# spi_v3.net
KiCad netlist of a schematic drawn in EAGLE
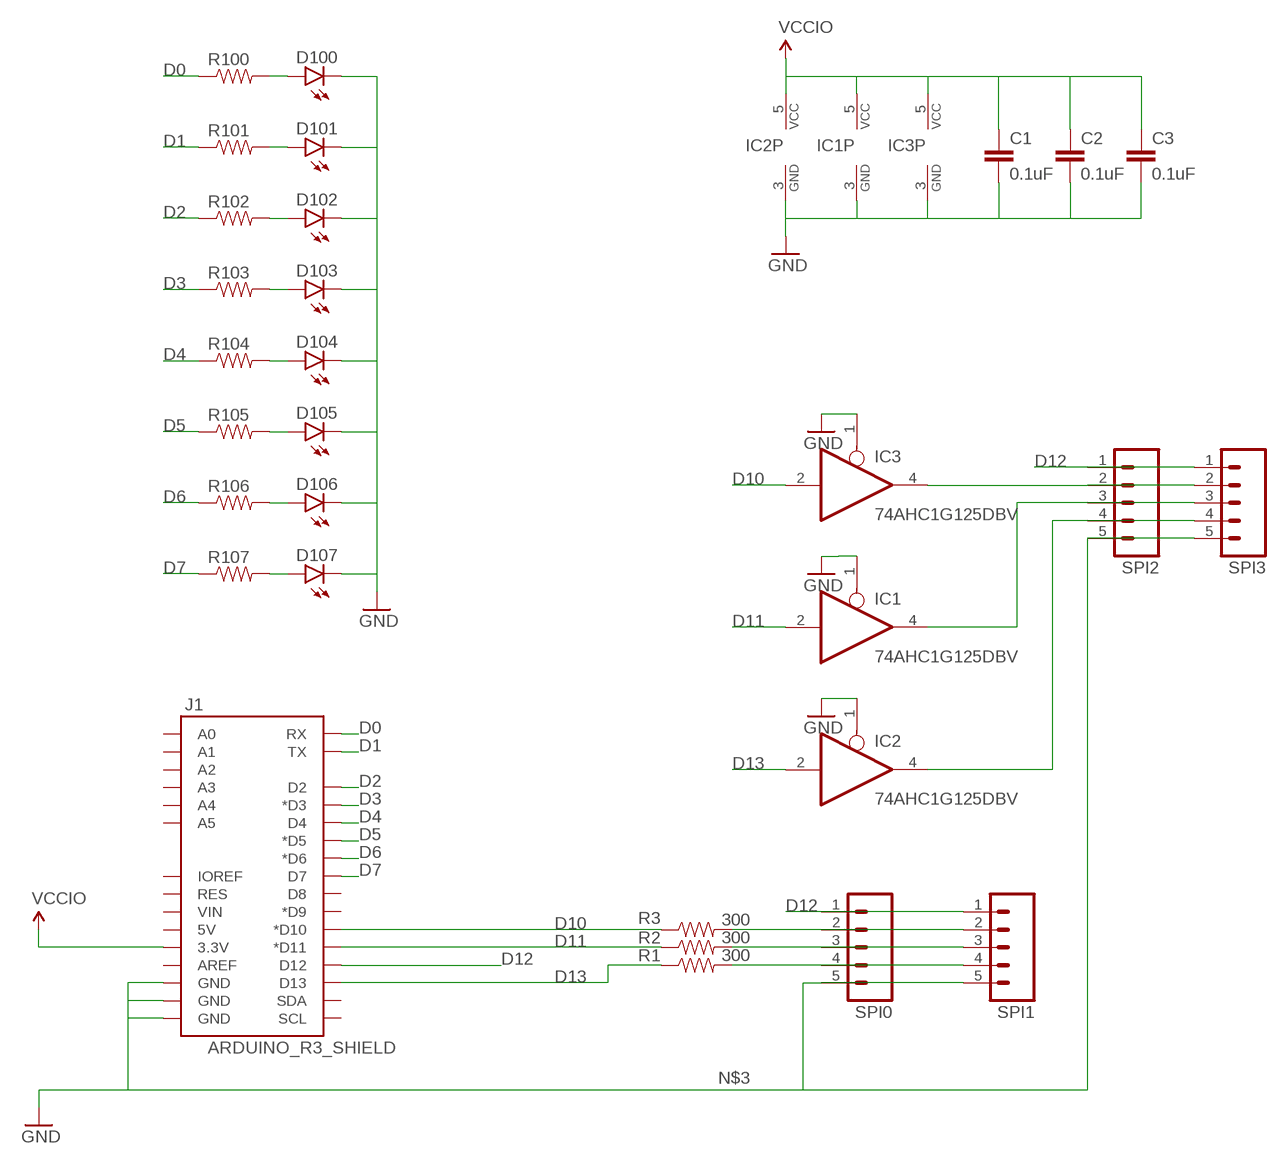
[diagram p0: schematic, sheet 1]

(export (version "E")
  (design (tool "Eeschema 10.0.6"))
  (components
    (comp (ref "C1")
      (value "0.1uF")
      (footprint "eagle-import:0402-CAP")
      (libsource (lib "eagle-import") (part "0.1UF-16V(+-10%)(0402)"))
    )
    (comp (ref "C2")
      (value "0.1uF")
      (footprint "eagle-import:0402-CAP")
      (libsource (lib "eagle-import") (part "0.1UF-16V(+-10%)(0402)"))
    )
    (comp (ref "C3")
      (value "0.1uF")
      (footprint "eagle-import:0402-CAP")
      (libsource (lib "eagle-import") (part "0.1UF-16V(+-10%)(0402)"))
    )
    (comp (ref "D100")
      (value "LED-FKIT-1206")
      (footprint "eagle-import:FKIT-LED-1206")
      (libsource (lib "eagle-import") (part "LED-FKIT-1206"))
    )
    (comp (ref "D101")
      (value "LED-FKIT-1206")
      (footprint "eagle-import:FKIT-LED-1206")
      (libsource (lib "eagle-import") (part "LED-FKIT-1206"))
    )
    (comp (ref "D102")
      (value "LED-FKIT-1206")
      (footprint "eagle-import:FKIT-LED-1206")
      (libsource (lib "eagle-import") (part "LED-FKIT-1206"))
    )
    (comp (ref "D103")
      (value "LED-FKIT-1206")
      (footprint "eagle-import:FKIT-LED-1206")
      (libsource (lib "eagle-import") (part "LED-FKIT-1206"))
    )
    (comp (ref "D104")
      (value "LED-FKIT-1206")
      (footprint "eagle-import:FKIT-LED-1206")
      (libsource (lib "eagle-import") (part "LED-FKIT-1206"))
    )
    (comp (ref "D105")
      (value "LED-FKIT-1206")
      (footprint "eagle-import:FKIT-LED-1206")
      (libsource (lib "eagle-import") (part "LED-FKIT-1206"))
    )
    (comp (ref "D106")
      (value "LED-FKIT-1206")
      (footprint "eagle-import:FKIT-LED-1206")
      (libsource (lib "eagle-import") (part "LED-FKIT-1206"))
    )
    (comp (ref "D107")
      (value "LED-FKIT-1206")
      (footprint "eagle-import:FKIT-LED-1206")
      (libsource (lib "eagle-import") (part "LED-FKIT-1206"))
    )
    (comp (ref "IC1")
      (value "74AHC1G125DBV")
      (footprint "eagle-import:SOT23-5")
      (libsource (lib "eagle-import") (part "741G125DBVAHC"))
    )
    (comp (ref "IC2")
      (value "74AHC1G125DBV")
      (footprint "eagle-import:SOT23-5")
      (libsource (lib "eagle-import") (part "741G125DBVAHC"))
    )
    (comp (ref "IC3")
      (value "74AHC1G125DBV")
      (footprint "eagle-import:SOT23-5")
      (libsource (lib "eagle-import") (part "741G125DBVAHC"))
    )
    (comp (ref "J1")
      (value "ARDUINO_R3_SHIELD")
      (footprint "eagle-import:UNO_R3_SHIELD")
      (libsource (lib "eagle-import") (part "ARDUINO_R3_SHIELD"))
    )
    (comp (ref "R1")
      (value "300")
      (footprint "eagle-import:AXIAL-0.4")
      (libsource (lib "eagle-import") (part "RESISTORPTH-1/4W"))
    )
    (comp (ref "R2")
      (value "300")
      (footprint "eagle-import:AXIAL-0.4")
      (libsource (lib "eagle-import") (part "RESISTORPTH-1/4W"))
    )
    (comp (ref "R3")
      (value "300")
      (footprint "eagle-import:AXIAL-0.4")
      (libsource (lib "eagle-import") (part "RESISTORPTH-1/4W"))
    )
    (comp (ref "R100")
      (value "RESISTOR0805-RES")
      (footprint "eagle-import:0805")
      (libsource (lib "eagle-import") (part "RESISTOR0805-RES"))
    )
    (comp (ref "R101")
      (value "RESISTOR0805-RES")
      (footprint "eagle-import:0805")
      (libsource (lib "eagle-import") (part "RESISTOR0805-RES"))
    )
    (comp (ref "R102")
      (value "RESISTOR0805-RES")
      (footprint "eagle-import:0805")
      (libsource (lib "eagle-import") (part "RESISTOR0805-RES"))
    )
    (comp (ref "R103")
      (value "RESISTOR0805-RES")
      (footprint "eagle-import:0805")
      (libsource (lib "eagle-import") (part "RESISTOR0805-RES"))
    )
    (comp (ref "R104")
      (value "RESISTOR0805-RES")
      (footprint "eagle-import:0805")
      (libsource (lib "eagle-import") (part "RESISTOR0805-RES"))
    )
    (comp (ref "R105")
      (value "RESISTOR0805-RES")
      (footprint "eagle-import:0805")
      (libsource (lib "eagle-import") (part "RESISTOR0805-RES"))
    )
    (comp (ref "R106")
      (value "RESISTOR0805-RES")
      (footprint "eagle-import:0805")
      (libsource (lib "eagle-import") (part "RESISTOR0805-RES"))
    )
    (comp (ref "R107")
      (value "RESISTOR0805-RES")
      (footprint "eagle-import:0805")
      (libsource (lib "eagle-import") (part "RESISTOR0805-RES"))
    )
    (comp (ref "SPI0")
      (value "M05PTH_LONGPADS")
      (footprint "eagle-import:1X05_LONGPADS")
      (libsource (lib "eagle-import") (part "M05PTH_LONGPADS"))
    )
    (comp (ref "SPI1")
      (value "M05PTH_LONGPADS")
      (footprint "eagle-import:1X05_LONGPADS")
      (libsource (lib "eagle-import") (part "M05PTH_LONGPADS"))
    )
    (comp (ref "SPI2")
      (value "M05PTH_LONGPADS")
      (footprint "eagle-import:1X05_LONGPADS")
      (libsource (lib "eagle-import") (part "M05PTH_LONGPADS"))
    )
    (comp (ref "SPI3")
      (value "M05PTH_LONGPADS")
      (footprint "eagle-import:1X05_LONGPADS")
      (libsource (lib "eagle-import") (part "M05PTH_LONGPADS"))
    )
  )
  (nets
    (net (code "1") (name "/D0") (class "Default")
      (node (ref "J1") (pin "RX") (pinfunction "RX_RX") (pintype "bidirectional"))
      (node (ref "R100") (pin "1") (pinfunction "1_1") (pintype "passive"))
    )
    (net (code "2") (name "/D1") (class "Default")
      (node (ref "J1") (pin "TX") (pinfunction "TX_TX") (pintype "bidirectional"))
      (node (ref "R101") (pin "1") (pinfunction "1_1") (pintype "passive"))
    )
    (net (code "3") (name "/D2") (class "Default")
      (node (ref "J1") (pin "D2") (pinfunction "D2_D2") (pintype "bidirectional"))
      (node (ref "R102") (pin "1") (pinfunction "1_1") (pintype "passive"))
    )
    (net (code "4") (name "/D3") (class "Default")
      (node (ref "J1") (pin "D3") (pinfunction "*D3_D3") (pintype "bidirectional"))
      (node (ref "R103") (pin "1") (pinfunction "1_1") (pintype "passive"))
    )
    (net (code "5") (name "/D4") (class "Default")
      (node (ref "J1") (pin "D4") (pinfunction "D4_D4") (pintype "bidirectional"))
      (node (ref "R104") (pin "1") (pinfunction "1_1") (pintype "passive"))
    )
    (net (code "6") (name "/D5") (class "Default")
      (node (ref "J1") (pin "D5") (pinfunction "*D5_D5") (pintype "bidirectional"))
      (node (ref "R105") (pin "1") (pinfunction "1_1") (pintype "passive"))
    )
    (net (code "7") (name "/D6") (class "Default")
      (node (ref "J1") (pin "D6") (pinfunction "*D6_D6") (pintype "bidirectional"))
      (node (ref "R106") (pin "1") (pinfunction "1_1") (pintype "passive"))
    )
    (net (code "8") (name "/D7") (class "Default")
      (node (ref "J1") (pin "D7") (pinfunction "D7_D7") (pintype "bidirectional"))
      (node (ref "R107") (pin "1") (pinfunction "1_1") (pintype "passive"))
    )
    (net (code "9") (name "/D10") (class "Default")
      (node (ref "IC3") (pin "2") (pinfunction "I_2") (pintype "input"))
      (node (ref "J1") (pin "D10") (pinfunction "*D10_D10") (pintype "bidirectional"))
      (node (ref "R3") (pin "P$1") (pinfunction "1_P$1") (pintype "passive"))
    )
    (net (code "10") (name "/D11") (class "Default")
      (node (ref "IC1") (pin "2") (pinfunction "I_2") (pintype "input"))
      (node (ref "J1") (pin "D11") (pinfunction "*D11_D11") (pintype "bidirectional"))
      (node (ref "R2") (pin "P$1") (pinfunction "1_P$1") (pintype "passive"))
    )
    (net (code "11") (name "/D12") (class "Default")
      (node (ref "J1") (pin "D12") (pinfunction "D12_D12") (pintype "bidirectional"))
      (node (ref "SPI0") (pin "1") (pinfunction "1_1") (pintype "passive"))
      (node (ref "SPI1") (pin "1") (pinfunction "1_1") (pintype "passive"))
      (node (ref "SPI2") (pin "1") (pinfunction "1_1") (pintype "passive"))
      (node (ref "SPI3") (pin "1") (pinfunction "1_1") (pintype "passive"))
    )
    (net (code "12") (name "/D13") (class "Default")
      (node (ref "IC2") (pin "2") (pinfunction "I_2") (pintype "input"))
      (node (ref "J1") (pin "D13") (pinfunction "D13_D13") (pintype "bidirectional"))
      (node (ref "R1") (pin "P$1") (pinfunction "1_P$1") (pintype "passive"))
    )
    (net (code "13") (name "GND") (class "Default")
      (node (ref "C1") (pin "2") (pinfunction "2_2") (pintype "passive"))
      (node (ref "C2") (pin "2") (pinfunction "2_2") (pintype "passive"))
      (node (ref "C3") (pin "2") (pinfunction "2_2") (pintype "passive"))
      (node (ref "D100") (pin "C") (pinfunction "C_C") (pintype "passive"))
      (node (ref "D101") (pin "C") (pinfunction "C_C") (pintype "passive"))
      (node (ref "D102") (pin "C") (pinfunction "C_C") (pintype "passive"))
      (node (ref "D103") (pin "C") (pinfunction "C_C") (pintype "passive"))
      (node (ref "D104") (pin "C") (pinfunction "C_C") (pintype "passive"))
      (node (ref "D105") (pin "C") (pinfunction "C_C") (pintype "passive"))
      (node (ref "D106") (pin "C") (pinfunction "C_C") (pintype "passive"))
      (node (ref "D107") (pin "C") (pinfunction "C_C") (pintype "passive"))
      (node (ref "IC1") (pin "1") (pinfunction "OE_1") (pintype "input"))
      (node (ref "IC1") (pin "3") (pinfunction "GND_3") (pintype "power_in"))
      (node (ref "IC2") (pin "1") (pinfunction "OE_1") (pintype "input"))
      (node (ref "IC2") (pin "3") (pinfunction "GND_3") (pintype "power_in"))
      (node (ref "IC3") (pin "1") (pinfunction "OE_1") (pintype "input"))
      (node (ref "IC3") (pin "3") (pinfunction "GND_3") (pintype "power_in"))
      (node (ref "J1") (pin "GND@0") (pinfunction "GND_GND@0") (pintype "bidirectional"))
      (node (ref "J1") (pin "GND@1") (pinfunction "GND_GND@1") (pintype "bidirectional"))
      (node (ref "J1") (pin "GND@2") (pinfunction "GND_GND@2") (pintype "bidirectional"))
      (node (ref "SPI0") (pin "5") (pinfunction "5_5") (pintype "passive"))
      (node (ref "SPI1") (pin "5") (pinfunction "5_5") (pintype "passive"))
      (node (ref "SPI2") (pin "5") (pinfunction "5_5") (pintype "passive"))
      (node (ref "SPI3") (pin "5") (pinfunction "5_5") (pintype "passive"))
    )
    (net (code "14") (name "Net-(D100-PadA)") (class "Default")
      (node (ref "D100") (pin "A") (pinfunction "A_A") (pintype "passive"))
      (node (ref "R100") (pin "2") (pinfunction "2_2") (pintype "passive"))
    )
    (net (code "15") (name "Net-(D101-PadA)") (class "Default")
      (node (ref "D101") (pin "A") (pinfunction "A_A") (pintype "passive"))
      (node (ref "R101") (pin "2") (pinfunction "2_2") (pintype "passive"))
    )
    (net (code "16") (name "Net-(D102-PadA)") (class "Default")
      (node (ref "D102") (pin "A") (pinfunction "A_A") (pintype "passive"))
      (node (ref "R102") (pin "2") (pinfunction "2_2") (pintype "passive"))
    )
    (net (code "17") (name "Net-(D103-PadA)") (class "Default")
      (node (ref "D103") (pin "A") (pinfunction "A_A") (pintype "passive"))
      (node (ref "R103") (pin "2") (pinfunction "2_2") (pintype "passive"))
    )
    (net (code "18") (name "Net-(D104-PadA)") (class "Default")
      (node (ref "D104") (pin "A") (pinfunction "A_A") (pintype "passive"))
      (node (ref "R104") (pin "2") (pinfunction "2_2") (pintype "passive"))
    )
    (net (code "19") (name "Net-(D105-PadA)") (class "Default")
      (node (ref "D105") (pin "A") (pinfunction "A_A") (pintype "passive"))
      (node (ref "R105") (pin "2") (pinfunction "2_2") (pintype "passive"))
    )
    (net (code "20") (name "Net-(D106-PadA)") (class "Default")
      (node (ref "D106") (pin "A") (pinfunction "A_A") (pintype "passive"))
      (node (ref "R106") (pin "2") (pinfunction "2_2") (pintype "passive"))
    )
    (net (code "21") (name "Net-(D107-PadA)") (class "Default")
      (node (ref "D107") (pin "A") (pinfunction "A_A") (pintype "passive"))
      (node (ref "R107") (pin "2") (pinfunction "2_2") (pintype "passive"))
    )
    (net (code "22") (name "Net-(IC1A-O)") (class "Default")
      (node (ref "IC1") (pin "4") (pinfunction "O_4") (pintype "tri_state"))
      (node (ref "SPI2") (pin "3") (pinfunction "3_3") (pintype "passive"))
      (node (ref "SPI3") (pin "3") (pinfunction "3_3") (pintype "passive"))
    )
    (net (code "23") (name "Net-(IC2A-O)") (class "Default")
      (node (ref "IC2") (pin "4") (pinfunction "O_4") (pintype "tri_state"))
      (node (ref "SPI2") (pin "4") (pinfunction "4_4") (pintype "passive"))
      (node (ref "SPI3") (pin "4") (pinfunction "4_4") (pintype "passive"))
    )
    (net (code "24") (name "Net-(IC3A-O)") (class "Default")
      (node (ref "IC3") (pin "4") (pinfunction "O_4") (pintype "tri_state"))
      (node (ref "SPI2") (pin "2") (pinfunction "2_2") (pintype "passive"))
      (node (ref "SPI3") (pin "2") (pinfunction "2_2") (pintype "passive"))
    )
    (net (code "25") (name "Net-(R1-2)") (class "Default")
      (node (ref "R1") (pin "P$2") (pinfunction "2_P$2") (pintype "passive"))
      (node (ref "SPI0") (pin "4") (pinfunction "4_4") (pintype "passive"))
      (node (ref "SPI1") (pin "4") (pinfunction "4_4") (pintype "passive"))
    )
    (net (code "26") (name "Net-(R2-2)") (class "Default")
      (node (ref "R2") (pin "P$2") (pinfunction "2_P$2") (pintype "passive"))
      (node (ref "SPI0") (pin "3") (pinfunction "3_3") (pintype "passive"))
      (node (ref "SPI1") (pin "3") (pinfunction "3_3") (pintype "passive"))
    )
    (net (code "27") (name "Net-(R3-2)") (class "Default")
      (node (ref "R3") (pin "P$2") (pinfunction "2_P$2") (pintype "passive"))
      (node (ref "SPI0") (pin "2") (pinfunction "2_2") (pintype "passive"))
      (node (ref "SPI1") (pin "2") (pinfunction "2_2") (pintype "passive"))
    )
    (net (code "28") (name "VCCIO") (class "Default")
      (node (ref "C1") (pin "1") (pinfunction "1_1") (pintype "passive"))
      (node (ref "C2") (pin "1") (pinfunction "1_1") (pintype "passive"))
      (node (ref "C3") (pin "1") (pinfunction "1_1") (pintype "passive"))
      (node (ref "IC1") (pin "5") (pinfunction "VCC_5") (pintype "power_in"))
      (node (ref "IC2") (pin "5") (pinfunction "VCC_5") (pintype "power_in"))
      (node (ref "IC3") (pin "5") (pinfunction "VCC_5") (pintype "power_in"))
      (node (ref "J1") (pin "3.3V") (pinfunction "3.3V_3.3V") (pintype "bidirectional"))
    )
    (net (code "29") (name "unconnected-(J1-*D9-PadD9)") (class "Default")
      (node (ref "J1") (pin "D9") (pinfunction "*D9_D9") (pintype "bidirectional"))
    )
    (net (code "30") (name "unconnected-(J1-Pad5V)") (class "Default")
      (node (ref "J1") (pin "5V") (pinfunction "5V_5V") (pintype "bidirectional"))
    )
    (net (code "31") (name "unconnected-(J1-PadA0)") (class "Default")
      (node (ref "J1") (pin "A0") (pinfunction "A0_A0") (pintype "bidirectional"))
    )
    (net (code "32") (name "unconnected-(J1-PadA1)") (class "Default")
      (node (ref "J1") (pin "A1") (pinfunction "A1_A1") (pintype "bidirectional"))
    )
    (net (code "33") (name "unconnected-(J1-PadA2)") (class "Default")
      (node (ref "J1") (pin "A2") (pinfunction "A2_A2") (pintype "bidirectional"))
    )
    (net (code "34") (name "unconnected-(J1-PadA3)") (class "Default")
      (node (ref "J1") (pin "A3") (pinfunction "A3_A3") (pintype "bidirectional"))
    )
    (net (code "35") (name "unconnected-(J1-PadA4)") (class "Default")
      (node (ref "J1") (pin "A4") (pinfunction "A4_A4") (pintype "bidirectional"))
    )
    (net (code "36") (name "unconnected-(J1-PadA5)") (class "Default")
      (node (ref "J1") (pin "A5") (pinfunction "A5_A5") (pintype "bidirectional"))
    )
    (net (code "37") (name "unconnected-(J1-PadAREF)") (class "Default")
      (node (ref "J1") (pin "AREF") (pinfunction "AREF_AREF") (pintype "bidirectional"))
    )
    (net (code "38") (name "unconnected-(J1-PadD8)") (class "Default")
      (node (ref "J1") (pin "D8") (pinfunction "D8_D8") (pintype "bidirectional"))
    )
    (net (code "39") (name "unconnected-(J1-PadIOREF)") (class "Default")
      (node (ref "J1") (pin "IOREF") (pinfunction "IOREF_IOREF") (pintype "bidirectional"))
    )
    (net (code "40") (name "unconnected-(J1-PadRES)") (class "Default")
      (node (ref "J1") (pin "RES") (pinfunction "RES_RES") (pintype "bidirectional"))
    )
    (net (code "41") (name "unconnected-(J1-PadSCL)") (class "Default")
      (node (ref "J1") (pin "SCL") (pinfunction "SCL_SCL") (pintype "bidirectional"))
    )
    (net (code "42") (name "unconnected-(J1-PadSDA)") (class "Default")
      (node (ref "J1") (pin "SDA") (pinfunction "SDA_SDA") (pintype "bidirectional"))
    )
    (net (code "43") (name "unconnected-(J1-PadVIN)") (class "Default")
      (node (ref "J1") (pin "VIN") (pinfunction "VIN_VIN") (pintype "bidirectional"))
    )
  )
)
